# S111E.net
KiCad netlist of a schematic drawn in EAGLE
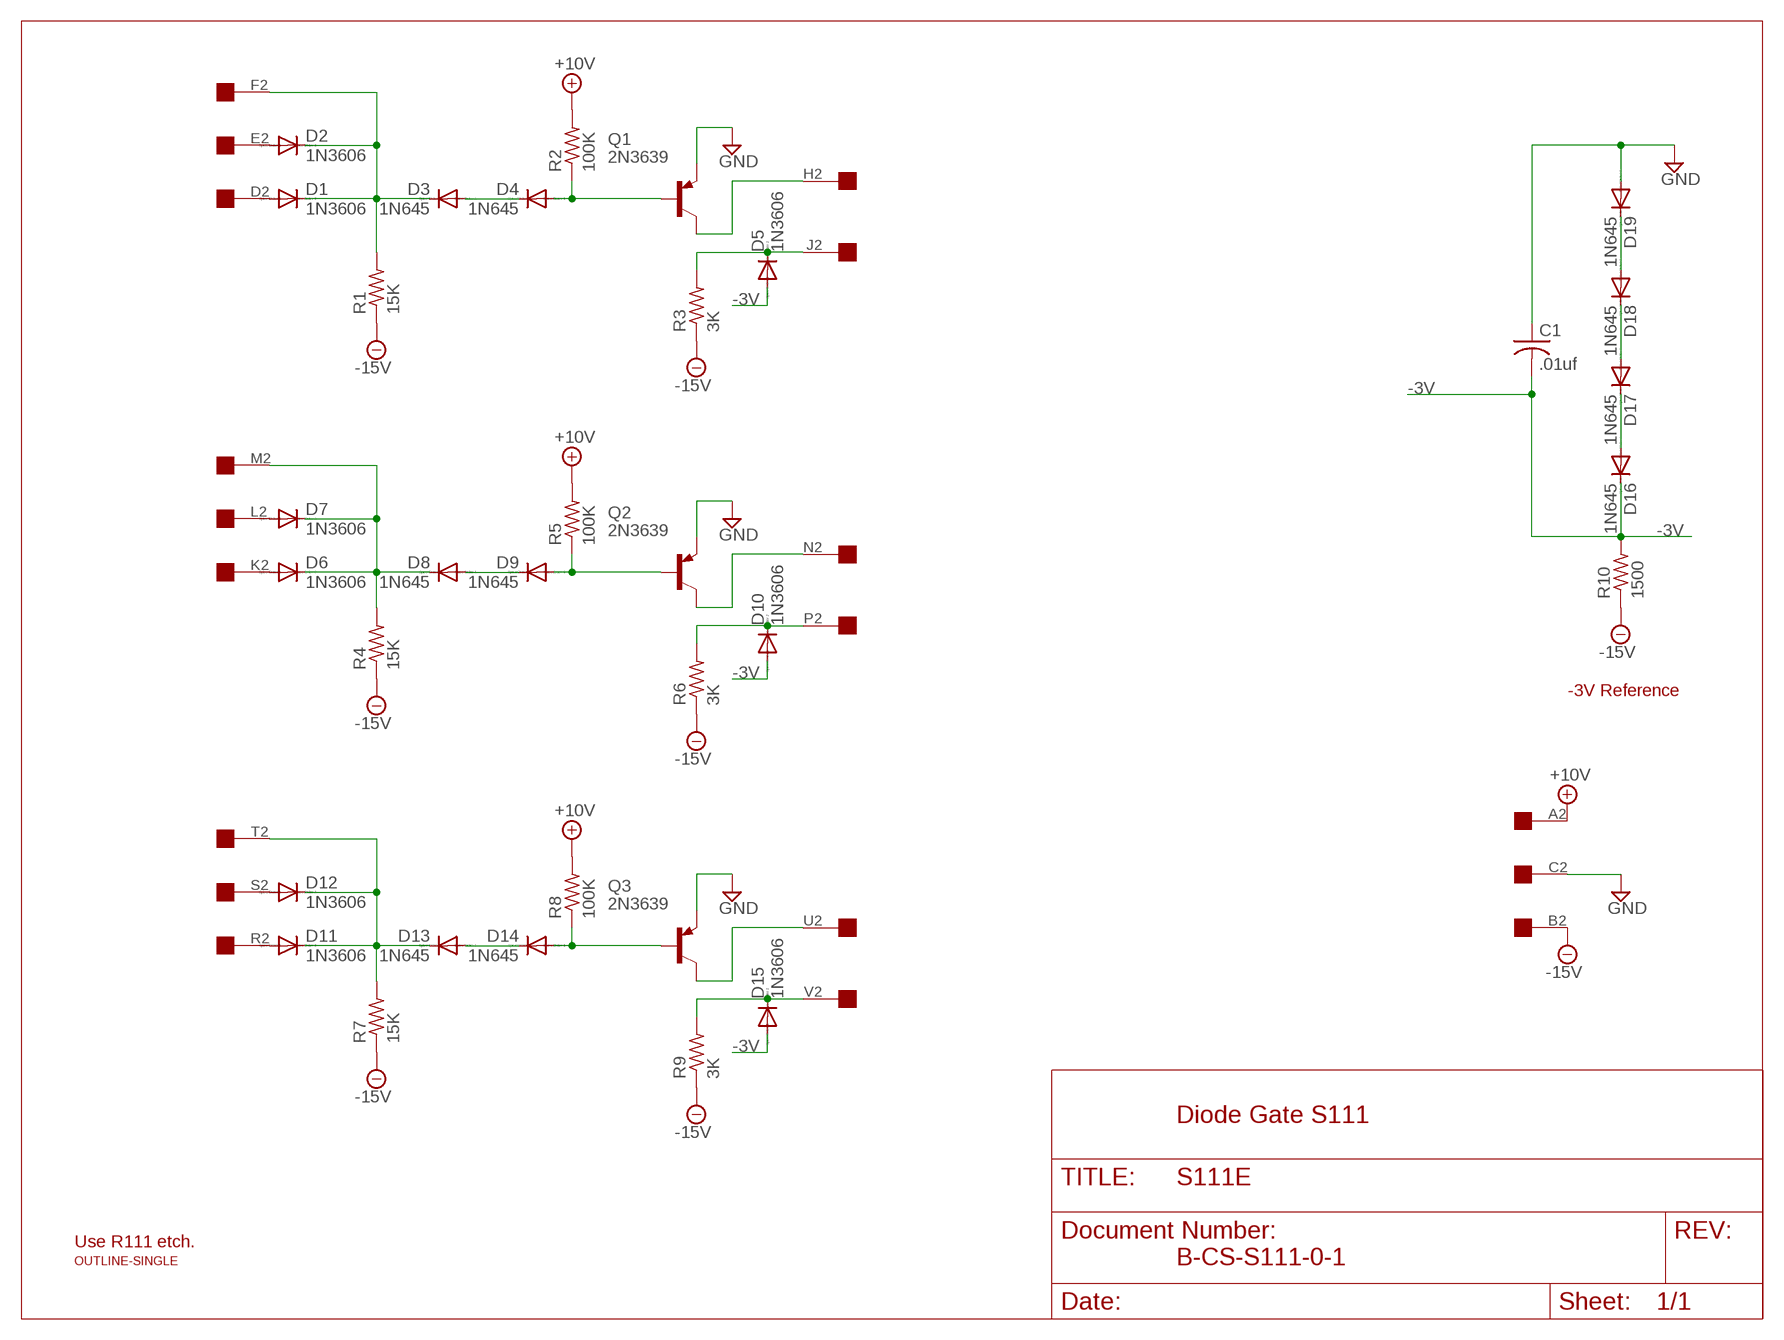
[diagram p0: schematic, sheet 1]

(export (version "E")
  (design (tool "Eeschema 10.0.6"))
  (components
    (comp (ref "C1")
      (value ".01uf")
      (footprint "eagle-import:C050-025X075")
      (libsource (lib "eagle-import") (part "C-US050-025X075"))
    )
    (comp (ref "D1")
      (value "1N3606")
      (footprint "eagle-import:DO35-10")
      (libsource (lib "eagle-import") (part "1N4148DO35-10"))
    )
    (comp (ref "D2")
      (value "1N3606")
      (footprint "eagle-import:DO35-10")
      (libsource (lib "eagle-import") (part "1N4148DO35-10"))
    )
    (comp (ref "D3")
      (value "1N645")
      (footprint "eagle-import:DO35-10")
      (libsource (lib "eagle-import") (part "1N4148DO35-10"))
    )
    (comp (ref "D4")
      (value "1N645")
      (footprint "eagle-import:DO35-10")
      (libsource (lib "eagle-import") (part "1N4148DO35-10"))
    )
    (comp (ref "D5")
      (value "1N3606")
      (footprint "eagle-import:DO35-10")
      (libsource (lib "eagle-import") (part "1N4148DO35-10"))
    )
    (comp (ref "D6")
      (value "1N3606")
      (footprint "eagle-import:DO35-10")
      (libsource (lib "eagle-import") (part "1N4148DO35-10"))
    )
    (comp (ref "D7")
      (value "1N3606")
      (footprint "eagle-import:DO35-10")
      (libsource (lib "eagle-import") (part "1N4148DO35-10"))
    )
    (comp (ref "D8")
      (value "1N645")
      (footprint "eagle-import:DO35-10")
      (libsource (lib "eagle-import") (part "1N4148DO35-10"))
    )
    (comp (ref "D9")
      (value "1N645")
      (footprint "eagle-import:DO35-10")
      (libsource (lib "eagle-import") (part "1N4148DO35-10"))
    )
    (comp (ref "D10")
      (value "1N3606")
      (footprint "eagle-import:DO35-10")
      (libsource (lib "eagle-import") (part "1N4148DO35-10"))
    )
    (comp (ref "D11")
      (value "1N3606")
      (footprint "eagle-import:DO35-10")
      (libsource (lib "eagle-import") (part "1N4148DO35-10"))
    )
    (comp (ref "D12")
      (value "1N3606")
      (footprint "eagle-import:DO35-10")
      (libsource (lib "eagle-import") (part "1N4148DO35-10"))
    )
    (comp (ref "D13")
      (value "1N645")
      (footprint "eagle-import:DO35-10")
      (libsource (lib "eagle-import") (part "1N4148DO35-10"))
    )
    (comp (ref "D14")
      (value "1N645")
      (footprint "eagle-import:DO35-10")
      (libsource (lib "eagle-import") (part "1N4148DO35-10"))
    )
    (comp (ref "D15")
      (value "1N3606")
      (footprint "eagle-import:DO35-10")
      (libsource (lib "eagle-import") (part "1N4148DO35-10"))
    )
    (comp (ref "D16")
      (value "1N645")
      (footprint "eagle-import:DO35-10")
      (libsource (lib "eagle-import") (part "1N4148DO35-10"))
    )
    (comp (ref "D17")
      (value "1N645")
      (footprint "eagle-import:DO35-10")
      (libsource (lib "eagle-import") (part "1N4148DO35-10"))
    )
    (comp (ref "D18")
      (value "1N645")
      (footprint "eagle-import:DO35-10")
      (libsource (lib "eagle-import") (part "1N4148DO35-10"))
    )
    (comp (ref "D19")
      (value "1N645")
      (footprint "eagle-import:DO35-10")
      (libsource (lib "eagle-import") (part "1N4148DO35-10"))
    )
    (comp (ref "Q1")
      (value "2N3639")
      (footprint "eagle-import:TO39")
      (libsource (lib "eagle-import") (part "2N3637"))
    )
    (comp (ref "Q2")
      (value "2N3639")
      (footprint "eagle-import:TO39")
      (libsource (lib "eagle-import") (part "2N3637"))
    )
    (comp (ref "Q3")
      (value "2N3639")
      (footprint "eagle-import:TO39")
      (libsource (lib "eagle-import") (part "2N3637"))
    )
    (comp (ref "R1")
      (value "15K")
      (footprint "eagle-import:0207_10")
      (libsource (lib "eagle-import") (part "R-US_0207/10"))
    )
    (comp (ref "R2")
      (value "100K")
      (footprint "eagle-import:0207_10")
      (libsource (lib "eagle-import") (part "R-US_0207/10"))
    )
    (comp (ref "R3")
      (value "3K")
      (footprint "eagle-import:0207_10")
      (libsource (lib "eagle-import") (part "R-US_0207/10"))
    )
    (comp (ref "R4")
      (value "15K")
      (footprint "eagle-import:0207_10")
      (libsource (lib "eagle-import") (part "R-US_0207/10"))
    )
    (comp (ref "R5")
      (value "100K")
      (footprint "eagle-import:0207_10")
      (libsource (lib "eagle-import") (part "R-US_0207/10"))
    )
    (comp (ref "R6")
      (value "3K")
      (footprint "eagle-import:0207_10")
      (libsource (lib "eagle-import") (part "R-US_0207/10"))
    )
    (comp (ref "R7")
      (value "15K")
      (footprint "eagle-import:0207_10")
      (libsource (lib "eagle-import") (part "R-US_0207/10"))
    )
    (comp (ref "R8")
      (value "100K")
      (footprint "eagle-import:0207_10")
      (libsource (lib "eagle-import") (part "R-US_0207/10"))
    )
    (comp (ref "R9")
      (value "3K")
      (footprint "eagle-import:0207_10")
      (libsource (lib "eagle-import") (part "R-US_0207/10"))
    )
    (comp (ref "R10")
      (value "1500")
      (footprint "eagle-import:0207_10")
      (libsource (lib "eagle-import") (part "R-US_0207/10"))
    )
    (comp (ref "U$1")
      (value "OUTLINE-SINGLE")
      (footprint "eagle-import:SINGLE")
      (libsource (lib "eagle-import") (part "OUTLINE-SINGLE"))
    )
    (comp (ref "U$2")
      (value "EDGE-1")
      (footprint "eagle-import:EDGE-CON1")
      (libsource (lib "eagle-import") (part "EDGE-1"))
    )
  )
  (nets
    (net (code "1") (name "+10V") (class "Default")
      (node (ref "R2") (pin "2") (pinfunction "2_2") (pintype "passive"))
      (node (ref "R5") (pin "2") (pinfunction "2_2") (pintype "passive"))
      (node (ref "R8") (pin "2") (pinfunction "2_2") (pintype "passive"))
      (node (ref "U$2") (pin "A2") (pinfunction "1_A2") (pintype "bidirectional"))
    )
    (net (code "2") (name "-15V") (class "Default")
      (node (ref "R1") (pin "1") (pinfunction "1_1") (pintype "passive"))
      (node (ref "R10") (pin "1") (pinfunction "1_1") (pintype "passive"))
      (node (ref "R3") (pin "1") (pinfunction "1_1") (pintype "passive"))
      (node (ref "R4") (pin "1") (pinfunction "1_1") (pintype "passive"))
      (node (ref "R6") (pin "1") (pinfunction "1_1") (pintype "passive"))
      (node (ref "R7") (pin "1") (pinfunction "1_1") (pintype "passive"))
      (node (ref "R9") (pin "1") (pinfunction "1_1") (pintype "passive"))
      (node (ref "U$2") (pin "B2") (pinfunction "1_B2") (pintype "bidirectional"))
    )
    (net (code "3") (name "/-3V") (class "Default")
      (node (ref "C1") (pin "2") (pinfunction "2_2") (pintype "passive"))
      (node (ref "D10") (pin "A") (pinfunction "A_A") (pintype "passive"))
      (node (ref "D15") (pin "A") (pinfunction "A_A") (pintype "passive"))
      (node (ref "D16") (pin "C") (pinfunction "C_C") (pintype "passive"))
      (node (ref "D5") (pin "A") (pinfunction "A_A") (pintype "passive"))
      (node (ref "R10") (pin "2") (pinfunction "2_2") (pintype "passive"))
    )
    (net (code "4") (name "GND") (class "Default")
      (node (ref "C1") (pin "1") (pinfunction "1_1") (pintype "passive"))
      (node (ref "D19") (pin "A") (pinfunction "A_A") (pintype "passive"))
      (node (ref "Q1") (pin "1") (pinfunction "E_1") (pintype "passive"))
      (node (ref "Q2") (pin "1") (pinfunction "E_1") (pintype "passive"))
      (node (ref "Q3") (pin "1") (pinfunction "E_1") (pintype "passive"))
      (node (ref "U$2") (pin "C2") (pinfunction "1_C2") (pintype "bidirectional"))
    )
    (net (code "5") (name "Net-(D3-PadA)") (class "Default")
      (node (ref "D3") (pin "A") (pinfunction "A_A") (pintype "passive"))
      (node (ref "D4") (pin "C") (pinfunction "C_C") (pintype "passive"))
    )
    (net (code "6") (name "Net-(D8-PadA)") (class "Default")
      (node (ref "D8") (pin "A") (pinfunction "A_A") (pintype "passive"))
      (node (ref "D9") (pin "C") (pinfunction "C_C") (pintype "passive"))
    )
    (net (code "7") (name "Net-(D13-PadA)") (class "Default")
      (node (ref "D13") (pin "A") (pinfunction "A_A") (pintype "passive"))
      (node (ref "D14") (pin "C") (pinfunction "C_C") (pintype "passive"))
    )
    (net (code "8") (name "Net-(D16-PadA)") (class "Default")
      (node (ref "D16") (pin "A") (pinfunction "A_A") (pintype "passive"))
      (node (ref "D17") (pin "C") (pinfunction "C_C") (pintype "passive"))
    )
    (net (code "9") (name "Net-(D17-PadA)") (class "Default")
      (node (ref "D17") (pin "A") (pinfunction "A_A") (pintype "passive"))
      (node (ref "D18") (pin "C") (pinfunction "C_C") (pintype "passive"))
    )
    (net (code "10") (name "Net-(D18-PadA)") (class "Default")
      (node (ref "D18") (pin "A") (pinfunction "A_A") (pintype "passive"))
      (node (ref "D19") (pin "C") (pinfunction "C_C") (pintype "passive"))
    )
    (net (code "11") (name "Net-(Q1-B)") (class "Default")
      (node (ref "D4") (pin "A") (pinfunction "A_A") (pintype "passive"))
      (node (ref "Q1") (pin "2") (pinfunction "B_2") (pintype "passive"))
      (node (ref "R2") (pin "1") (pinfunction "1_1") (pintype "passive"))
    )
    (net (code "12") (name "Net-(Q1-C)") (class "Default")
      (node (ref "Q1") (pin "3") (pinfunction "C_3") (pintype "passive"))
      (node (ref "U$2") (pin "H2") (pinfunction "1_H2") (pintype "bidirectional"))
    )
    (net (code "13") (name "Net-(Q2-B)") (class "Default")
      (node (ref "D9") (pin "A") (pinfunction "A_A") (pintype "passive"))
      (node (ref "Q2") (pin "2") (pinfunction "B_2") (pintype "passive"))
      (node (ref "R5") (pin "1") (pinfunction "1_1") (pintype "passive"))
    )
    (net (code "14") (name "Net-(Q2-C)") (class "Default")
      (node (ref "Q2") (pin "3") (pinfunction "C_3") (pintype "passive"))
      (node (ref "U$2") (pin "N2") (pinfunction "1_N2") (pintype "bidirectional"))
    )
    (net (code "15") (name "Net-(Q3-B)") (class "Default")
      (node (ref "D14") (pin "A") (pinfunction "A_A") (pintype "passive"))
      (node (ref "Q3") (pin "2") (pinfunction "B_2") (pintype "passive"))
      (node (ref "R8") (pin "1") (pinfunction "1_1") (pintype "passive"))
    )
    (net (code "16") (name "Net-(Q3-C)") (class "Default")
      (node (ref "Q3") (pin "3") (pinfunction "C_3") (pintype "passive"))
      (node (ref "U$2") (pin "U2") (pinfunction "1_U2") (pintype "bidirectional"))
    )
    (net (code "17") (name "Net-(U$2D-1)") (class "Default")
      (node (ref "D1") (pin "A") (pinfunction "A_A") (pintype "passive"))
      (node (ref "U$2") (pin "D2") (pinfunction "1_D2") (pintype "bidirectional"))
    )
    (net (code "18") (name "Net-(U$2E-1)") (class "Default")
      (node (ref "D2") (pin "A") (pinfunction "A_A") (pintype "passive"))
      (node (ref "U$2") (pin "E2") (pinfunction "1_E2") (pintype "bidirectional"))
    )
    (net (code "19") (name "Net-(U$2F-1)") (class "Default")
      (node (ref "D1") (pin "C") (pinfunction "C_C") (pintype "passive"))
      (node (ref "D2") (pin "C") (pinfunction "C_C") (pintype "passive"))
      (node (ref "D3") (pin "C") (pinfunction "C_C") (pintype "passive"))
      (node (ref "R1") (pin "2") (pinfunction "2_2") (pintype "passive"))
      (node (ref "U$2") (pin "F2") (pinfunction "1_F2") (pintype "bidirectional"))
    )
    (net (code "20") (name "Net-(U$2H-1)") (class "Default")
      (node (ref "D5") (pin "C") (pinfunction "C_C") (pintype "passive"))
      (node (ref "R3") (pin "2") (pinfunction "2_2") (pintype "passive"))
      (node (ref "U$2") (pin "J2") (pinfunction "1_J2") (pintype "bidirectional"))
    )
    (net (code "21") (name "Net-(U$2I-1)") (class "Default")
      (node (ref "D6") (pin "A") (pinfunction "A_A") (pintype "passive"))
      (node (ref "U$2") (pin "K2") (pinfunction "1_K2") (pintype "bidirectional"))
    )
    (net (code "22") (name "Net-(U$2J-1)") (class "Default")
      (node (ref "D7") (pin "A") (pinfunction "A_A") (pintype "passive"))
      (node (ref "U$2") (pin "L2") (pinfunction "1_L2") (pintype "bidirectional"))
    )
    (net (code "23") (name "Net-(U$2K-1)") (class "Default")
      (node (ref "D6") (pin "C") (pinfunction "C_C") (pintype "passive"))
      (node (ref "D7") (pin "C") (pinfunction "C_C") (pintype "passive"))
      (node (ref "D8") (pin "C") (pinfunction "C_C") (pintype "passive"))
      (node (ref "R4") (pin "2") (pinfunction "2_2") (pintype "passive"))
      (node (ref "U$2") (pin "M2") (pinfunction "1_M2") (pintype "bidirectional"))
    )
    (net (code "24") (name "Net-(U$2M-1)") (class "Default")
      (node (ref "D10") (pin "C") (pinfunction "C_C") (pintype "passive"))
      (node (ref "R6") (pin "2") (pinfunction "2_2") (pintype "passive"))
      (node (ref "U$2") (pin "P2") (pinfunction "1_P2") (pintype "bidirectional"))
    )
    (net (code "25") (name "Net-(U$2N-1)") (class "Default")
      (node (ref "D11") (pin "A") (pinfunction "A_A") (pintype "passive"))
      (node (ref "U$2") (pin "R2") (pinfunction "1_R2") (pintype "bidirectional"))
    )
    (net (code "26") (name "Net-(U$2O-1)") (class "Default")
      (node (ref "D12") (pin "A") (pinfunction "A_A") (pintype "passive"))
      (node (ref "U$2") (pin "S2") (pinfunction "1_S2") (pintype "bidirectional"))
    )
    (net (code "27") (name "Net-(U$2P-1)") (class "Default")
      (node (ref "D11") (pin "C") (pinfunction "C_C") (pintype "passive"))
      (node (ref "D12") (pin "C") (pinfunction "C_C") (pintype "passive"))
      (node (ref "D13") (pin "C") (pinfunction "C_C") (pintype "passive"))
      (node (ref "R7") (pin "2") (pinfunction "2_2") (pintype "passive"))
      (node (ref "U$2") (pin "T2") (pinfunction "1_T2") (pintype "bidirectional"))
    )
    (net (code "28") (name "Net-(U$2R-1)") (class "Default")
      (node (ref "D15") (pin "C") (pinfunction "C_C") (pintype "passive"))
      (node (ref "R9") (pin "2") (pinfunction "2_2") (pintype "passive"))
      (node (ref "U$2") (pin "V2") (pinfunction "1_V2") (pintype "bidirectional"))
    )
  )
)
